# AutoOff.net
KiCad netlist of a schematic drawn in EAGLE
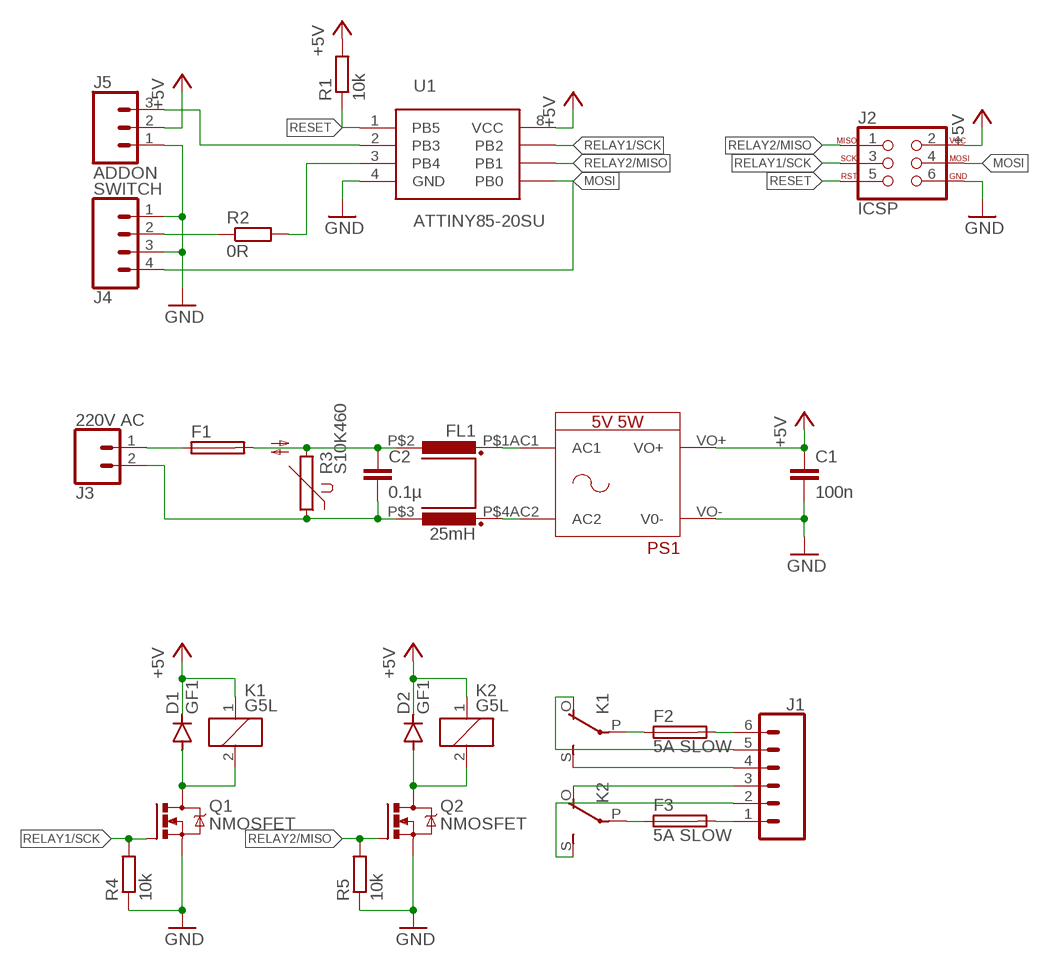
[diagram p0: schematic, sheet 1]

(export (version "E")
  (design (tool "Eeschema 10.0.6"))
  (components
    (comp (ref "C1")
      (value "100n")
      (footprint "eagle-import:C0603")
      (libsource (lib "eagle-import") (part "C-EUC0603"))
    )
    (comp (ref "C2")
      (value "0.1µ")
      (footprint "eagle-import:C102-064X133")
      (libsource (lib "eagle-import") (part "C-EU102-064X133"))
    )
    (comp (ref "D1")
      (value "GF1")
      (footprint "eagle-import:SMA-DO214AC")
      (libsource (lib "eagle-import") (part "GF1"))
    )
    (comp (ref "D2")
      (value "GF1")
      (footprint "eagle-import:SMA-DO214AC")
      (libsource (lib "eagle-import") (part "GF1"))
    )
    (comp (ref "F1")
      (value "0.5A SLOW")
      (footprint "eagle-import:SH22,5A")
      (fields (field (name "MPN") "0031.7701.11"))
      (libsource (lib "eagle-import") (part "SH22,5A"))
    )
    (comp (ref "F2")
      (value "5A SLOW")
      (footprint "eagle-import:SH22,5A")
      (fields (field (name "MPN") "0031.7701.11"))
      (libsource (lib "eagle-import") (part "SH22,5A"))
    )
    (comp (ref "F3")
      (value "5A SLOW")
      (footprint "eagle-import:SH22,5A")
      (fields (field (name "MPN") "0031.7701.11"))
      (libsource (lib "eagle-import") (part "SH22,5A"))
    )
    (comp (ref "FL1")
      (value "25mH")
      (footprint "eagle-import:UU9.8-YH161014")
      (libsource (lib "eagle-import") (part "UU9.8-YH161014"))
    )
    (comp (ref "J1")
      (value "CONN_063.5MM-6")
      (footprint "eagle-import:SCREWTERMINAL-3.5MM-6")
      (libsource (lib "eagle-import") (part "CONN_063.5MM-6"))
    )
    (comp (ref "J2")
      (value "ICSP")
      (footprint "eagle-import:2X3_LOCK")
      (libsource (lib "eagle-import") (part "AVR_SPI_PROG_3X22X3_LOCK"))
    )
    (comp (ref "J3")
      (value "220V AC")
      (footprint "eagle-import:SCREWTERMINAL-3.5MM-2_LOCK")
      (libsource (lib "eagle-import") (part "CONN_023.5MM_LOCK"))
    )
    (comp (ref "J4")
      (value "SWITCH")
      (footprint "eagle-import:SCREWTERMINAL-3.5MM-4_LOCK")
      (libsource (lib "eagle-import") (part "CONN_04SCREW_LOCK"))
    )
    (comp (ref "J5")
      (value "ADDON")
      (footprint "eagle-import:SCREWTERMINAL-3.5MM-3_LOCK.007S")
      (libsource (lib "eagle-import") (part "CONN_03SCREW_LOCK"))
    )
    (comp (ref "K1")
      (value "G5L")
      (footprint "eagle-import:G5LE")
      (libsource (lib "eagle-import") (part "G5L"))
    )
    (comp (ref "K2")
      (value "G5L")
      (footprint "eagle-import:G5LE")
      (libsource (lib "eagle-import") (part "G5L"))
    )
    (comp (ref "PS1")
      (value "5V 5W")
      (footprint "eagle-import:HLK-5M")
      (libsource (lib "eagle-import") (part "HLK-5M05"))
    )
    (comp (ref "Q1")
      (value "NMOSFET")
      (footprint "eagle-import:SOT23")
      (libsource (lib "eagle-import") (part "NMOSFETSOT23_"))
    )
    (comp (ref "Q2")
      (value "NMOSFET")
      (footprint "eagle-import:SOT23")
      (libsource (lib "eagle-import") (part "NMOSFETSOT23_"))
    )
    (comp (ref "R1")
      (value "10k")
      (footprint "eagle-import:R0603")
      (libsource (lib "eagle-import") (part "R-EU_R0603"))
    )
    (comp (ref "R2")
      (value "0R")
      (footprint "eagle-import:R0603")
      (libsource (lib "eagle-import") (part "R-EU_R0603"))
    )
    (comp (ref "R3")
      (value "S10K460")
      (footprint "eagle-import:S10K460")
      (libsource (lib "eagle-import") (part "S10K460"))
    )
    (comp (ref "R4")
      (value "10k")
      (footprint "eagle-import:R0603")
      (libsource (lib "eagle-import") (part "R-EU_R0603"))
    )
    (comp (ref "R5")
      (value "10k")
      (footprint "eagle-import:R0603")
      (libsource (lib "eagle-import") (part "R-EU_R0603"))
    )
    (comp (ref "U1")
      (value "ATTINY85-20SU")
      (footprint "eagle-import:SOIC-8")
      (fields
        (field (name "DIGI_KEY_PART_NUMBER") "ATTINY85-20SU-ND")
        (field (name "MANUFACTURER") "Microchip Technology")
        (field (name "CREATED_BY") "PCBLayout.com")
      )
      (libsource (lib "eagle-import") (part "ATTINY85-20SU"))
    )
  )
  (nets
    (net (code "1") (name "+5V") (class "Default")
      (node (ref "C1") (pin "1") (pinfunction "1_1") (pintype "passive"))
      (node (ref "D1") (pin "K") (pinfunction "C_K") (pintype "passive"))
      (node (ref "D2") (pin "K") (pinfunction "C_K") (pintype "passive"))
      (node (ref "J2") (pin "2") (pinfunction "2_2") (pintype "passive"))
      (node (ref "J5") (pin "2") (pinfunction "2_2") (pintype "passive"))
      (node (ref "K1") (pin "1") (pinfunction "1_1") (pintype "passive"))
      (node (ref "K2") (pin "1") (pinfunction "1_1") (pintype "passive"))
      (node (ref "PS1") (pin "VO+") (pinfunction "VO+_VO+") (pintype "bidirectional"))
      (node (ref "R1") (pin "2") (pinfunction "2_2") (pintype "passive"))
      (node (ref "U1") (pin "8") (pinfunction "VCC_8") (pintype "power_in"))
    )
    (net (code "2") (name "GND") (class "Default")
      (node (ref "C1") (pin "2") (pinfunction "2_2") (pintype "passive"))
      (node (ref "J2") (pin "6") (pinfunction "6_6") (pintype "passive"))
      (node (ref "J4") (pin "1") (pinfunction "1_1") (pintype "passive"))
      (node (ref "J4") (pin "3") (pinfunction "3_3") (pintype "passive"))
      (node (ref "J5") (pin "1") (pinfunction "1_1") (pintype "passive"))
      (node (ref "PS1") (pin "VO-") (pinfunction "V0-_VO-") (pintype "bidirectional"))
      (node (ref "Q1") (pin "2") (pinfunction "S_2") (pintype "passive"))
      (node (ref "Q2") (pin "2") (pinfunction "S_2") (pintype "passive"))
      (node (ref "R4") (pin "1") (pinfunction "1_1") (pintype "passive"))
      (node (ref "R5") (pin "1") (pinfunction "1_1") (pintype "passive"))
      (node (ref "U1") (pin "4") (pinfunction "GND_4") (pintype "power_in"))
    )
    (net (code "3") (name "MOSI") (class "Default")
      (node (ref "J2") (pin "4") (pinfunction "4_4") (pintype "passive"))
      (node (ref "J4") (pin "4") (pinfunction "4_4") (pintype "passive"))
      (node (ref "U1") (pin "5") (pinfunction "PB0_5") (pintype "bidirectional"))
    )
    (net (code "4") (name "Net-(F1-Pad1)") (class "Default")
      (node (ref "F1") (pin "1") (pinfunction "1_1") (pintype "passive"))
      (node (ref "J3") (pin "1") (pinfunction "1_1") (pintype "passive"))
    )
    (net (code "5") (name "Net-(F2-Pad1)") (class "Default")
      (node (ref "F2") (pin "1") (pinfunction "1_1") (pintype "passive"))
      (node (ref "K1") (pin "P") (pinfunction "P_P") (pintype "passive"))
    )
    (net (code "6") (name "Net-(F2-Pad2)") (class "Default")
      (node (ref "F2") (pin "2") (pinfunction "2_2") (pintype "passive"))
      (node (ref "J1") (pin "6") (pinfunction "6_6") (pintype "passive"))
    )
    (net (code "7") (name "Net-(F3-Pad1)") (class "Default")
      (node (ref "F3") (pin "1") (pinfunction "1_1") (pintype "passive"))
      (node (ref "K2") (pin "P") (pinfunction "P_P") (pintype "passive"))
    )
    (net (code "8") (name "Net-(F3-Pad2)") (class "Default")
      (node (ref "F3") (pin "2") (pinfunction "2_2") (pintype "passive"))
      (node (ref "J1") (pin "1") (pinfunction "1_1") (pintype "passive"))
    )
    (net (code "9") (name "Net-(FL1-1)") (class "Default")
      (node (ref "FL1") (pin "P$1") (pinfunction "1_P$1") (pintype "passive"))
      (node (ref "PS1") (pin "AC1") (pinfunction "AC1_AC1") (pintype "bidirectional"))
    )
    (net (code "10") (name "Net-(FL1-2)") (class "Default")
      (node (ref "C2") (pin "1") (pinfunction "1_1") (pintype "passive"))
      (node (ref "F1") (pin "2") (pinfunction "2_2") (pintype "passive"))
      (node (ref "FL1") (pin "P$2") (pinfunction "2_P$2") (pintype "passive"))
      (node (ref "R3") (pin "2") (pinfunction "2_2") (pintype "passive"))
    )
    (net (code "11") (name "Net-(FL1-3)") (class "Default")
      (node (ref "C2") (pin "2") (pinfunction "2_2") (pintype "passive"))
      (node (ref "FL1") (pin "P$3") (pinfunction "3_P$3") (pintype "passive"))
      (node (ref "J3") (pin "2") (pinfunction "2_2") (pintype "passive"))
      (node (ref "R3") (pin "1") (pinfunction "1_1") (pintype "passive"))
    )
    (net (code "12") (name "Net-(FL1-4)") (class "Default")
      (node (ref "FL1") (pin "P$4") (pinfunction "4_P$4") (pintype "passive"))
      (node (ref "PS1") (pin "AC2") (pinfunction "AC2_AC2") (pintype "bidirectional"))
    )
    (net (code "13") (name "Net-(J1-Pad2)") (class "Default")
      (node (ref "J1") (pin "2") (pinfunction "2_2") (pintype "passive"))
      (node (ref "K2") (pin "S") (pinfunction "S_S") (pintype "passive"))
    )
    (net (code "14") (name "Net-(J1-Pad3)") (class "Default")
      (node (ref "J1") (pin "3") (pinfunction "3_3") (pintype "passive"))
      (node (ref "K2") (pin "O") (pinfunction "O_O") (pintype "passive"))
    )
    (net (code "15") (name "Net-(J1-Pad4)") (class "Default")
      (node (ref "J1") (pin "4") (pinfunction "4_4") (pintype "passive"))
      (node (ref "K1") (pin "S") (pinfunction "S_S") (pintype "passive"))
    )
    (net (code "16") (name "Net-(J1-Pad5)") (class "Default")
      (node (ref "J1") (pin "5") (pinfunction "5_5") (pintype "passive"))
      (node (ref "K1") (pin "O") (pinfunction "O_O") (pintype "passive"))
    )
    (net (code "17") (name "Net-(J4-Pad2)") (class "Default")
      (node (ref "J4") (pin "2") (pinfunction "2_2") (pintype "passive"))
      (node (ref "R2") (pin "1") (pinfunction "1_1") (pintype "passive"))
    )
    (net (code "18") (name "Net-(Q1-D)") (class "Default")
      (node (ref "D1") (pin "A") (pinfunction "A_A") (pintype "passive"))
      (node (ref "K1") (pin "2") (pinfunction "2_2") (pintype "passive"))
      (node (ref "Q1") (pin "3") (pinfunction "D_3") (pintype "passive"))
    )
    (net (code "19") (name "Net-(Q2-D)") (class "Default")
      (node (ref "D2") (pin "A") (pinfunction "A_A") (pintype "passive"))
      (node (ref "K2") (pin "2") (pinfunction "2_2") (pintype "passive"))
      (node (ref "Q2") (pin "3") (pinfunction "D_3") (pintype "passive"))
    )
    (net (code "20") (name "Net-(U1-PB3)") (class "Default")
      (node (ref "J5") (pin "3") (pinfunction "3_3") (pintype "passive"))
      (node (ref "U1") (pin "2") (pinfunction "PB3_2") (pintype "bidirectional"))
    )
    (net (code "21") (name "Net-(U1-PB4)") (class "Default")
      (node (ref "R2") (pin "2") (pinfunction "2_2") (pintype "passive"))
      (node (ref "U1") (pin "3") (pinfunction "PB4_3") (pintype "bidirectional"))
    )
    (net (code "22") (name "RELAY1{slash}SCK") (class "Default")
      (node (ref "J2") (pin "3") (pinfunction "3_3") (pintype "passive"))
      (node (ref "Q1") (pin "1") (pinfunction "G_1") (pintype "passive"))
      (node (ref "R4") (pin "2") (pinfunction "2_2") (pintype "passive"))
      (node (ref "U1") (pin "7") (pinfunction "PB2_7") (pintype "bidirectional"))
    )
    (net (code "23") (name "RELAY2{slash}MISO") (class "Default")
      (node (ref "J2") (pin "1") (pinfunction "1_1") (pintype "passive"))
      (node (ref "Q2") (pin "1") (pinfunction "G_1") (pintype "passive"))
      (node (ref "R5") (pin "2") (pinfunction "2_2") (pintype "passive"))
      (node (ref "U1") (pin "6") (pinfunction "PB1_6") (pintype "bidirectional"))
    )
    (net (code "24") (name "RESET") (class "Default")
      (node (ref "J2") (pin "5") (pinfunction "5_5") (pintype "passive"))
      (node (ref "R1") (pin "1") (pinfunction "1_1") (pintype "passive"))
      (node (ref "U1") (pin "1") (pinfunction "PB5_1") (pintype "bidirectional"))
    )
  )
)
